# SALIDA_DAC.net
KiCad netlist of a schematic drawn in Altium Designer
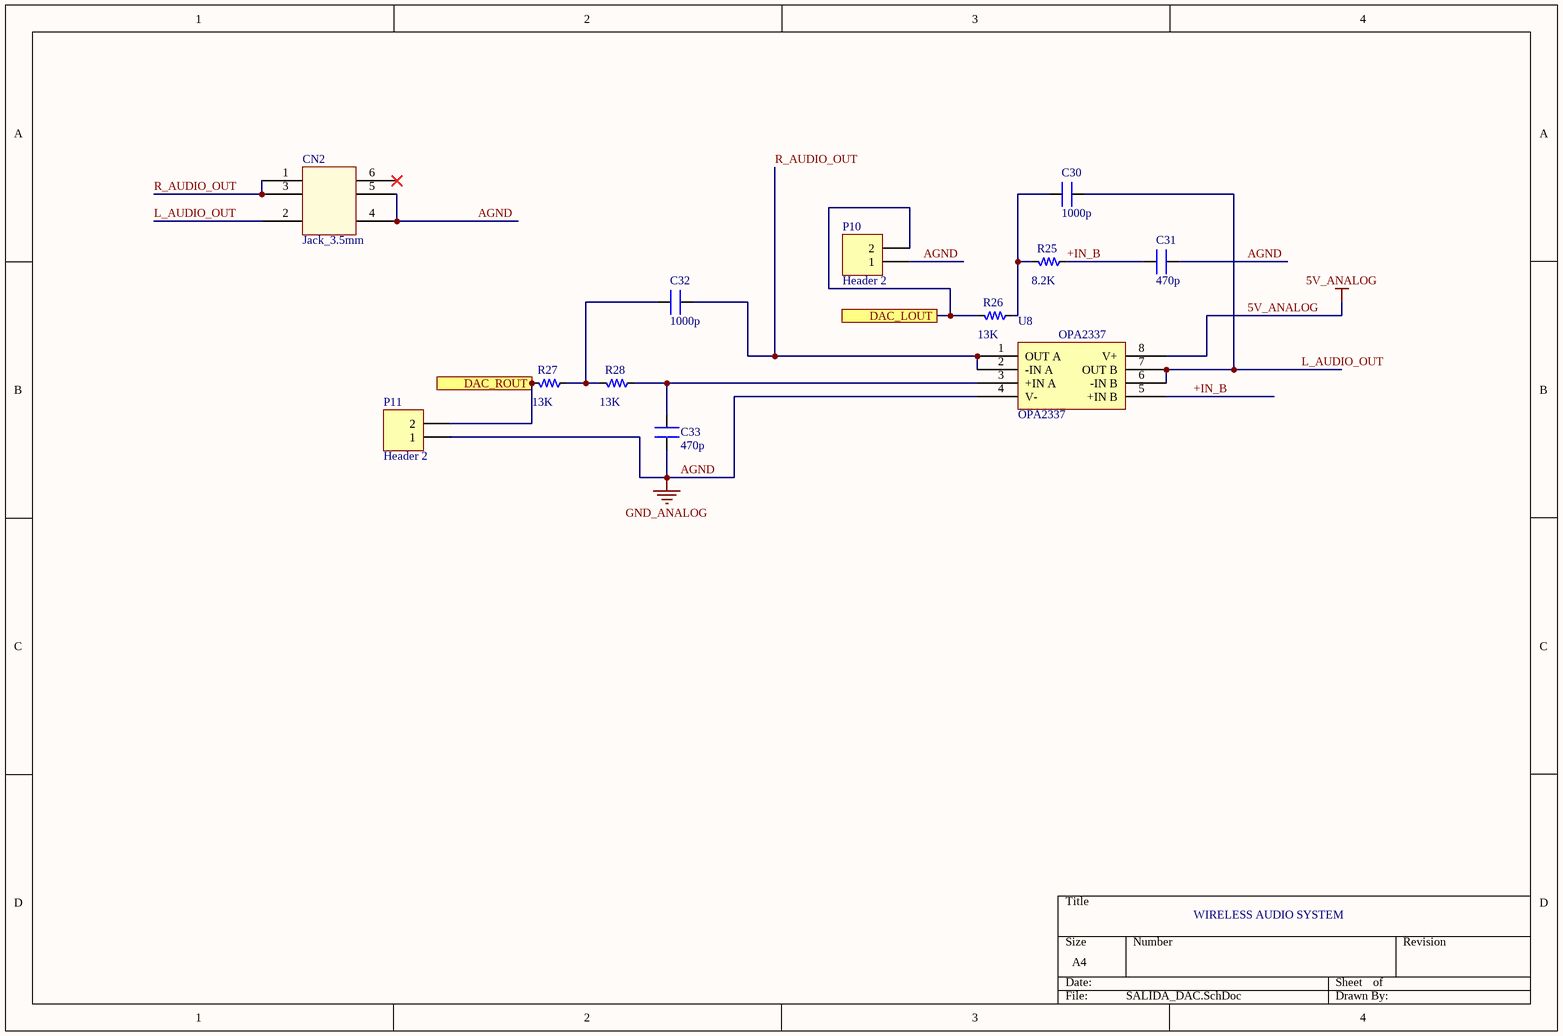
[diagram p0: SALIDA_DAC.SchDoc]

(export (version "E")
  (design (tool "Eeschema 10.0.6"))
  (components
    (comp (ref "C30")
      (value "1000p")
      (footprint "C_0805")
      (description "Non Polarised Capacitor")
      (libsource (lib "TD2_Project") (part "Capacitor_NP"))
    )
    (comp (ref "C31")
      (value "470p")
      (footprint "C_0805")
      (description "Non Polarised Capacitor")
      (libsource (lib "TD2_Project") (part "Capacitor_NP"))
    )
    (comp (ref "C32")
      (value "1000p")
      (footprint "C_0805")
      (description "Non Polarised Capacitor")
      (libsource (lib "TD2_Project") (part "Capacitor_NP"))
    )
    (comp (ref "C33")
      (value "470p")
      (footprint "C_0805")
      (description "Non Polarised Capacitor")
      (libsource (lib "TD2_Project") (part "Capacitor_NP"))
    )
    (comp (ref "CN2")
      (value "Jack_3.5mm")
      (footprint "JACK_3.5mm")
      (libsource (lib "TD2_Project") (part "Jack_3.5mm"))
    )
    (comp (ref "P10")
      (value "Header 2")
      (footprint "Header1x2")
      (description "Header, 2-Pin")
      (fields (field (name "PUBLISHER") "Altium Limited"))
      (libsource (lib "Miscellaneous Connectors") (part "Header 2"))
    )
    (comp (ref "P11")
      (value "Header 2")
      (footprint "Header1x2")
      (description "Header, 2-Pin")
      (fields (field (name "PUBLISHER") "Altium Limited"))
      (libsource (lib "Miscellaneous Connectors") (part "Header 2"))
    )
    (comp (ref "R25") (value "8.2K") (footprint "R_0805") (libsource (lib "TD2_Project") (part "Resistor")))
    (comp (ref "R26") (value "13K") (footprint "R_0805") (libsource (lib "TD2_Project") (part "Resistor")))
    (comp (ref "R27") (value "13K") (footprint "R_0805") (libsource (lib "TD2_Project") (part "Resistor")))
    (comp (ref "R28") (value "13K") (footprint "R_0805") (libsource (lib "TD2_Project") (part "Resistor")))
    (comp (ref "U8") (value "OPA2337") (footprint "SOIC-8N") (libsource (lib "TD2_Project") (part "OPA2337")))
  )
  (nets
    (net (code "1") (name "/+IN_B") (class "Default")
      (node (ref "C31") (pin "1") (pinfunction "1_1") (pintype "passive"))
      (node (ref "R25") (pin "2") (pinfunction "2_2") (pintype "passive"))
      (node (ref "U8") (pin "5") (pinfunction "+IN_B_5") (pintype "passive"))
    )
    (net (code "2") (name "/DAC_LOUT") (class "Default")
      (node (ref "P10") (pin "2") (pinfunction "2_2") (pintype "passive"))
      (node (ref "R26") (pin "1") (pinfunction "1_1") (pintype "passive"))
    )
    (net (code "3") (name "/DAC_ROUT") (class "Default")
      (node (ref "P11") (pin "2") (pinfunction "2_2") (pintype "passive"))
      (node (ref "R27") (pin "1") (pinfunction "1_1") (pintype "passive"))
    )
    (net (code "4") (name "/L_AUDIO_OUT") (class "Default")
      (node (ref "C30") (pin "2") (pinfunction "2_2") (pintype "passive"))
      (node (ref "CN2") (pin "2") (pintype "passive"))
      (node (ref "U8") (pin "6") (pinfunction "-IN_B_6") (pintype "passive"))
      (node (ref "U8") (pin "7") (pinfunction "OUT_B_7") (pintype "passive"))
    )
    (net (code "5") (name "/R_AUDIO_OUT") (class "Default")
      (node (ref "C32") (pin "2") (pinfunction "2_2") (pintype "passive"))
      (node (ref "CN2") (pin "1") (pintype "passive"))
      (node (ref "CN2") (pin "3") (pintype "passive"))
      (node (ref "U8") (pin "1") (pinfunction "OUT_A_1") (pintype "passive"))
      (node (ref "U8") (pin "2") (pinfunction "-IN_A_2") (pintype "passive"))
    )
    (net (code "6") (name "5V_ANALOG") (class "Default")
      (node (ref "U8") (pin "8") (pinfunction "V+_8") (pintype "passive"))
    )
    (net (code "7") (name "GND_ANALOG") (class "Default")
      (node (ref "C31") (pin "2") (pinfunction "2_2") (pintype "passive"))
      (node (ref "C33") (pin "2") (pinfunction "2_2") (pintype "passive"))
      (node (ref "CN2") (pin "4") (pintype "passive"))
      (node (ref "CN2") (pin "5") (pintype "passive"))
      (node (ref "P10") (pin "1") (pinfunction "1_1") (pintype "passive"))
      (node (ref "P11") (pin "1") (pinfunction "1_1") (pintype "passive"))
      (node (ref "U8") (pin "4") (pinfunction "V-_4") (pintype "passive"))
    )
    (net (code "8") (name "Net-(C30-Pad1)") (class "Default")
      (node (ref "C30") (pin "1") (pinfunction "1_1") (pintype "passive"))
      (node (ref "R25") (pin "1") (pinfunction "1_1") (pintype "passive"))
      (node (ref "R26") (pin "2") (pinfunction "2_2") (pintype "passive"))
    )
    (net (code "9") (name "Net-(C32-Pad1)") (class "Default")
      (node (ref "C32") (pin "1") (pinfunction "1_1") (pintype "passive"))
      (node (ref "R27") (pin "2") (pinfunction "2_2") (pintype "passive"))
      (node (ref "R28") (pin "1") (pinfunction "1_1") (pintype "passive"))
    )
    (net (code "10") (name "Net-(U8-+IN_A)") (class "Default")
      (node (ref "C33") (pin "1") (pinfunction "1_1") (pintype "passive"))
      (node (ref "R28") (pin "2") (pinfunction "2_2") (pintype "passive"))
      (node (ref "U8") (pin "3") (pinfunction "+IN_A_3") (pintype "passive"))
    )
    (net (code "11") (name "unconnected-(CN2-Pad6)") (class "Default")
      (node (ref "CN2") (pin "6") (pintype "passive+no_connect"))
    )
  )
)
